# WeatherStation.net
KiCad netlist of a schematic drawn in EAGLE
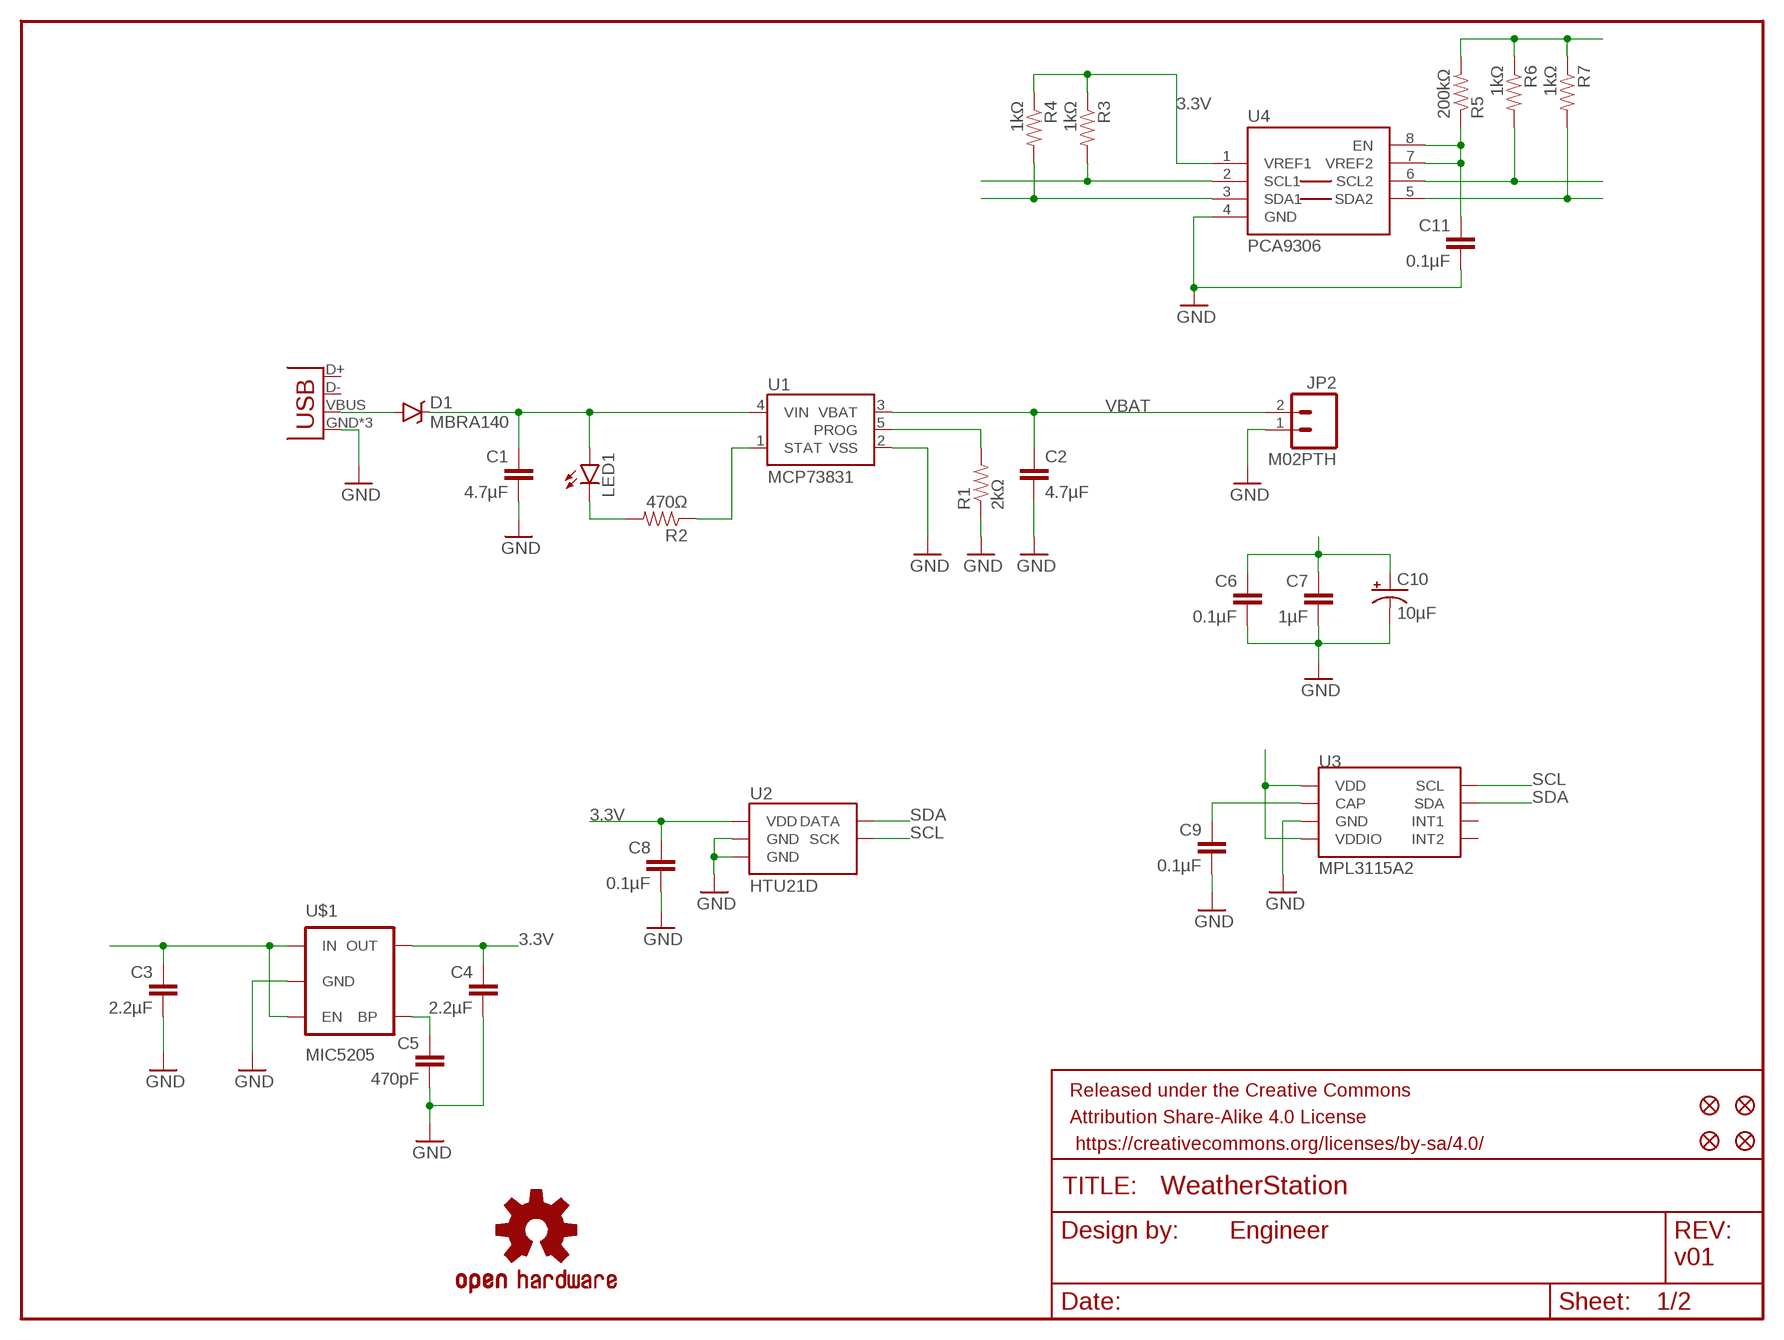
[diagram p0: schematic, sheet 1]
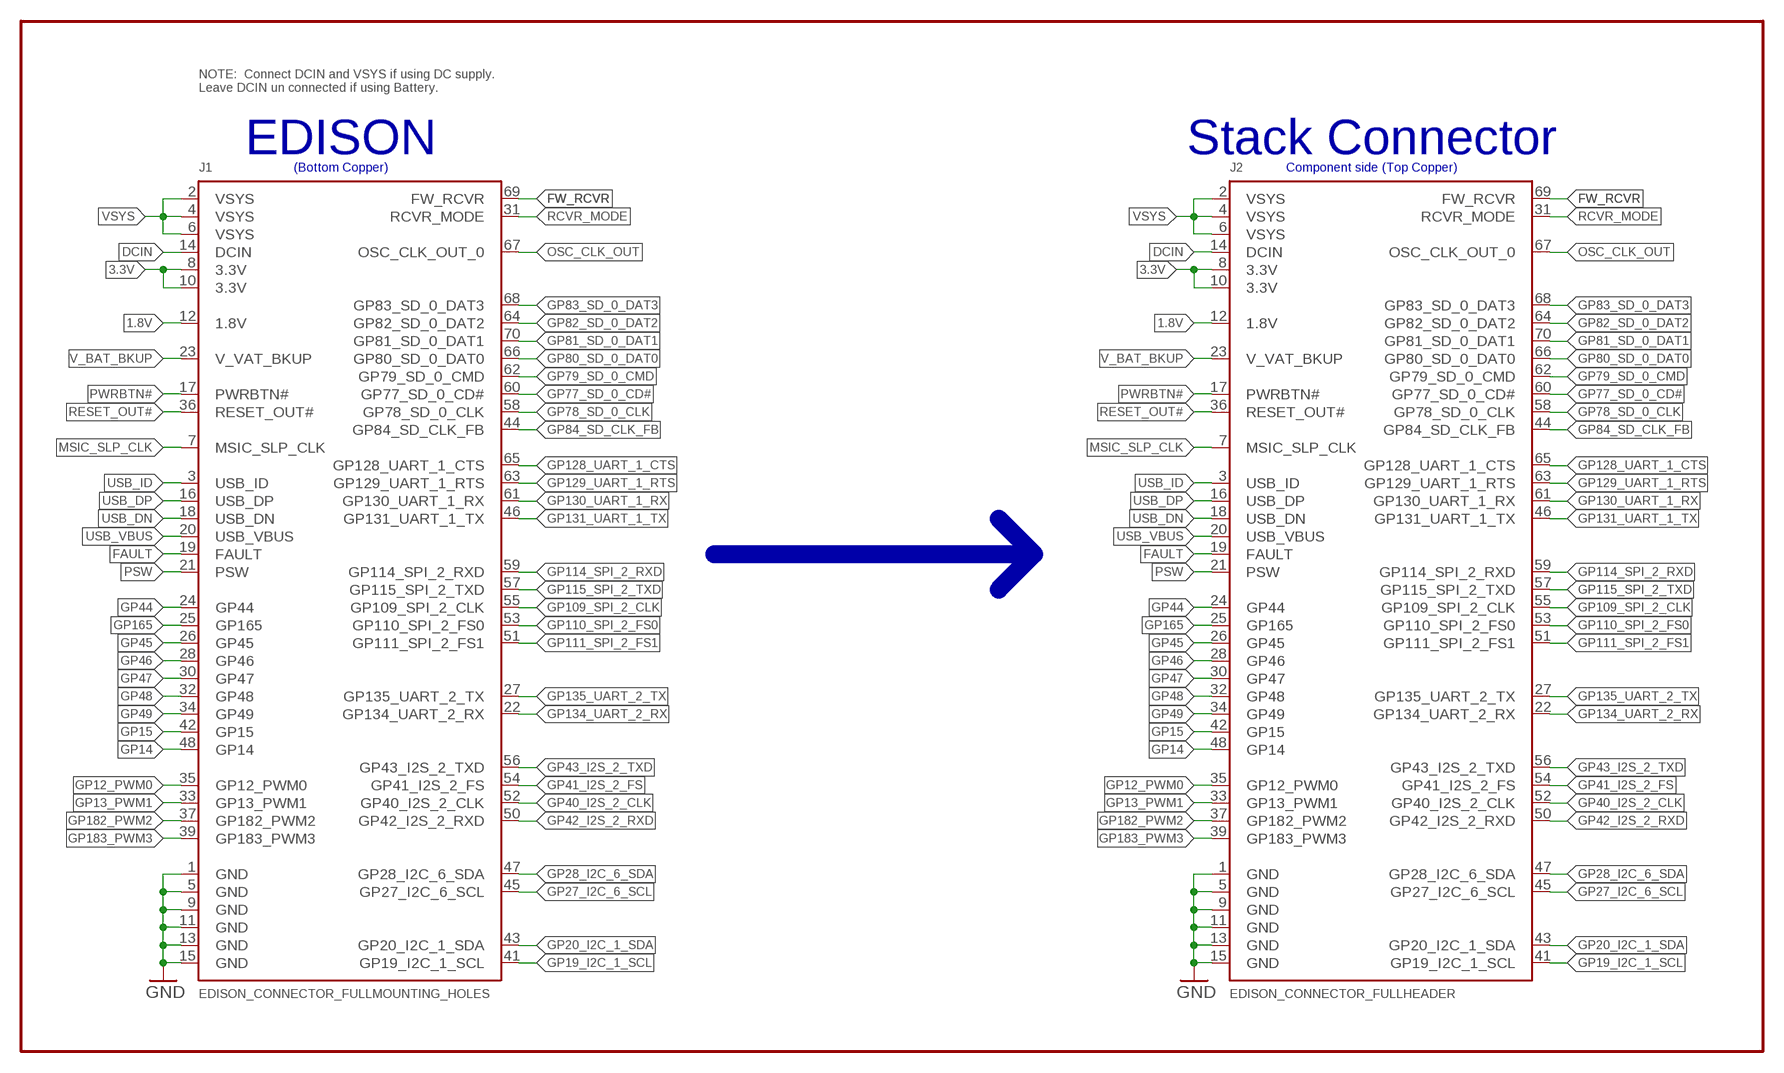
[diagram p1: schematic, sheet 2]

(export (version "E")
  (design (tool "Eeschema 10.0.6"))
  (components
    (comp (ref "C1")
      (value "4.7µF")
      (footprint "eagle-import:0805")
      (libsource (lib "eagle-import") (part "CAP0805"))
    )
    (comp (ref "C2")
      (value "4.7µF")
      (footprint "eagle-import:0805")
      (libsource (lib "eagle-import") (part "CAP0805"))
    )
    (comp (ref "C3")
      (value "2.2µF")
      (footprint "eagle-import:0805")
      (libsource (lib "eagle-import") (part "CAP0805"))
    )
    (comp (ref "C4")
      (value "2.2µF")
      (footprint "eagle-import:0805")
      (libsource (lib "eagle-import") (part "CAP0805"))
    )
    (comp (ref "C5")
      (value "470pF")
      (footprint "eagle-import:0805")
      (libsource (lib "eagle-import") (part "CAP0805"))
    )
    (comp (ref "C6")
      (value "0.1µF")
      (footprint "eagle-import:0805")
      (libsource (lib "eagle-import") (part "CAP0805"))
    )
    (comp (ref "C7")
      (value "1µF")
      (footprint "eagle-import:0805")
      (libsource (lib "eagle-import") (part "CAP0805"))
    )
    (comp (ref "C8")
      (value "0.1µF")
      (footprint "eagle-import:0805")
      (libsource (lib "eagle-import") (part "CAP0805"))
    )
    (comp (ref "C9")
      (value "0.1µF")
      (footprint "eagle-import:0805")
      (libsource (lib "eagle-import") (part "CAP0805"))
    )
    (comp (ref "C10")
      (value "10µF")
      (footprint "eagle-import:EIA3216")
      (libsource (lib "eagle-import") (part "CAP_POL1206"))
    )
    (comp (ref "C11")
      (value "0.1µF")
      (footprint "eagle-import:0805")
      (libsource (lib "eagle-import") (part "CAP0805"))
    )
    (comp (ref "D1")
      (value "MBRA140")
      (footprint "eagle-import:SMA-DIODE")
      (libsource (lib "eagle-import") (part "MBRA140"))
    )
    (comp (ref "FID1")
      (value "FIDUCIAL1X2")
      (footprint "eagle-import:FIDUCIAL-1X2")
      (libsource (lib "eagle-import") (part "FIDUCIAL1X2"))
    )
    (comp (ref "FID2")
      (value "FIDUCIAL1X2")
      (footprint "eagle-import:FIDUCIAL-1X2")
      (libsource (lib "eagle-import") (part "FIDUCIAL1X2"))
    )
    (comp (ref "FID3")
      (value "FIDUCIAL1X2")
      (footprint "eagle-import:FIDUCIAL-1X2")
      (libsource (lib "eagle-import") (part "FIDUCIAL1X2"))
    )
    (comp (ref "FID4")
      (value "FIDUCIAL1X2")
      (footprint "eagle-import:FIDUCIAL-1X2")
      (libsource (lib "eagle-import") (part "FIDUCIAL1X2"))
    )
    (comp (ref "FRAME1")
      (value "FRAME-LETTER")
      (footprint "eagle-import:CREATIVE_COMMONS")
      (libsource (lib "eagle-import") (part "FRAME-LETTER"))
    )
    (comp (ref "JP1")
      (value "USB-MICROB")
      (footprint "eagle-import:USB-MICROB")
      (libsource (lib "eagle-import") (part "USB-MICROB"))
    )
    (comp (ref "JP2")
      (value "M02PTH")
      (footprint "eagle-import:1X02")
      (libsource (lib "eagle-import") (part "M02PTH"))
    )
    (comp (ref "LED1")
      (value "LED0603")
      (footprint "eagle-import:LED-0603")
      (libsource (lib "eagle-import") (part "LED0603"))
    )
    (comp (ref "LOGO1")
      (value "OSHW-LOGOS")
      (footprint "eagle-import:OSHW-LOGO-S")
      (libsource (lib "eagle-import") (part "OSHW-LOGOS"))
    )
    (comp (ref "R1")
      (value "2kΩ")
      (footprint "eagle-import:0603-RES")
      (libsource (lib "eagle-import") (part "RESISTOR0603-RES"))
    )
    (comp (ref "R2")
      (value "470Ω")
      (footprint "eagle-import:0603-RES")
      (libsource (lib "eagle-import") (part "RESISTOR0603-RES"))
    )
    (comp (ref "R3")
      (value "1kΩ")
      (footprint "eagle-import:0603-RES")
      (libsource (lib "eagle-import") (part "RESISTOR0603-RES"))
    )
    (comp (ref "R4")
      (value "1kΩ")
      (footprint "eagle-import:0603-RES")
      (libsource (lib "eagle-import") (part "RESISTOR0603-RES"))
    )
    (comp (ref "R5")
      (value "200kΩ")
      (footprint "eagle-import:0603-RES")
      (libsource (lib "eagle-import") (part "RESISTOR0603-RES"))
    )
    (comp (ref "R6")
      (value "1kΩ")
      (footprint "eagle-import:0603-RES")
      (libsource (lib "eagle-import") (part "RESISTOR0603-RES"))
    )
    (comp (ref "R7")
      (value "1kΩ")
      (footprint "eagle-import:0603-RES")
      (libsource (lib "eagle-import") (part "RESISTOR0603-RES"))
    )
    (comp (ref "U$1")
      (value "MIC5205")
      (footprint "eagle-import:SOT23-5")
      (libsource (lib "eagle-import") (part "V_REG_MIC52053.3V"))
    )
    (comp (ref "U1")
      (value "MCP73831")
      (footprint "eagle-import:SOT23-5")
      (libsource (lib "eagle-import") (part "MCP73831"))
    )
    (comp (ref "U2")
      (value "HTU21D")
      (footprint "eagle-import:HTU21D")
      (libsource (lib "eagle-import") (part "HTU21DSMD"))
    )
    (comp (ref "U3")
      (value "MPL3115A2")
      (footprint "eagle-import:LGA8")
      (libsource (lib "eagle-import") (part "MPL3115A2LGA8"))
    )
    (comp (ref "U4")
      (value "PCA9306")
      (footprint "eagle-import:PSOP-8")
      (libsource (lib "eagle-import") (part "PCA9306"))
    )
    (comp (ref "J1")
      (value "EDISON_CONNECTOR_FULLMOUNTING_HOLES")
      (footprint "eagle-import:EDISON_DAUGHTER")
      (libsource (lib "eagle-import") (part "EDISON_CONNECTOR_FULLMOUNTING_HOLES"))
    )
    (comp (ref "J2")
      (value "EDISON_CONNECTOR_FULLHEADER")
      (footprint "eagle-import:DF40C-70DP-0.4(51)")
      (libsource (lib "eagle-import") (part "EDISON_CONNECTOR_FULLHEADER"))
    )
  )
  (nets
    (net (code "1") (name "1.8V") (class "Default")
      (node (ref "J1") (pin "12") (pinfunction "1.8V_12") (pintype "bidirectional"))
      (node (ref "J2") (pin "12") (pinfunction "1.8V_12") (pintype "bidirectional"))
      (node (ref "R5") (pin "2") (pinfunction "2_2") (pintype "passive"))
      (node (ref "R6") (pin "1") (pinfunction "1_1") (pintype "passive"))
      (node (ref "R7") (pin "1") (pinfunction "1_1") (pintype "passive"))
    )
    (net (code "2") (name "3.3V") (class "Default")
      (node (ref "C10") (pin "A") (pinfunction "+_A") (pintype "passive"))
      (node (ref "C4") (pin "1") (pinfunction "1_1") (pintype "passive"))
      (node (ref "C6") (pin "1") (pinfunction "1_1") (pintype "passive"))
      (node (ref "C7") (pin "1") (pinfunction "1_1") (pintype "passive"))
      (node (ref "C8") (pin "1") (pinfunction "1_1") (pintype "passive"))
      (node (ref "J1") (pin "10") (pinfunction "3.3V_10") (pintype "bidirectional"))
      (node (ref "J1") (pin "8") (pinfunction "3.3V_8") (pintype "bidirectional"))
      (node (ref "J2") (pin "10") (pinfunction "3.3V_10") (pintype "bidirectional"))
      (node (ref "J2") (pin "8") (pinfunction "3.3V_8") (pintype "bidirectional"))
      (node (ref "R3") (pin "1") (pinfunction "1_1") (pintype "passive"))
      (node (ref "R4") (pin "1") (pinfunction "1_1") (pintype "passive"))
      (node (ref "U$1") (pin "5") (pinfunction "OUT_5") (pintype "passive"))
      (node (ref "U2") (pin "VDD") (pinfunction "VDD_VDD") (pintype "power_in"))
      (node (ref "U3") (pin "1") (pinfunction "VDD_1") (pintype "power_in"))
      (node (ref "U3") (pin "4") (pinfunction "VDDIO_4") (pintype "power_in"))
      (node (ref "U4") (pin "1") (pinfunction "VREF1_1") (pintype "bidirectional"))
    )
    (net (code "3") (name "DCIN") (class "Default")
      (node (ref "J1") (pin "14") (pinfunction "DCIN_14") (pintype "bidirectional"))
      (node (ref "J2") (pin "14") (pinfunction "DCIN_14") (pintype "bidirectional"))
    )
    (net (code "4") (name "FAULT") (class "Default")
      (node (ref "J1") (pin "19") (pinfunction "FAULT_19") (pintype "bidirectional"))
      (node (ref "J2") (pin "19") (pinfunction "FAULT_19") (pintype "bidirectional"))
    )
    (net (code "5") (name "FW_RCVR") (class "Default")
      (node (ref "J1") (pin "69") (pinfunction "FW_RCVR_69") (pintype "bidirectional"))
      (node (ref "J2") (pin "69") (pinfunction "FW_RCVR_69") (pintype "bidirectional"))
    )
    (net (code "6") (name "GND") (class "Default")
      (node (ref "C1") (pin "2") (pinfunction "2_2") (pintype "passive"))
      (node (ref "C10") (pin "C") (pinfunction "-_C") (pintype "passive"))
      (node (ref "C11") (pin "2") (pinfunction "2_2") (pintype "passive"))
      (node (ref "C2") (pin "2") (pinfunction "2_2") (pintype "passive"))
      (node (ref "C3") (pin "2") (pinfunction "2_2") (pintype "passive"))
      (node (ref "C4") (pin "2") (pinfunction "2_2") (pintype "passive"))
      (node (ref "C5") (pin "2") (pinfunction "2_2") (pintype "passive"))
      (node (ref "C6") (pin "2") (pinfunction "2_2") (pintype "passive"))
      (node (ref "C7") (pin "2") (pinfunction "2_2") (pintype "passive"))
      (node (ref "C8") (pin "2") (pinfunction "2_2") (pintype "passive"))
      (node (ref "C9") (pin "2") (pinfunction "2_2") (pintype "passive"))
      (node (ref "J1") (pin "1") (pinfunction "GND_1") (pintype "bidirectional"))
      (node (ref "J1") (pin "11") (pinfunction "GND_11") (pintype "bidirectional"))
      (node (ref "J1") (pin "13") (pinfunction "GND_13") (pintype "bidirectional"))
      (node (ref "J1") (pin "15") (pinfunction "GND_15") (pintype "bidirectional"))
      (node (ref "J1") (pin "5") (pinfunction "GND_5") (pintype "bidirectional"))
      (node (ref "J1") (pin "9") (pinfunction "GND_9") (pintype "bidirectional"))
      (node (ref "J2") (pin "1") (pinfunction "GND_1") (pintype "bidirectional"))
      (node (ref "J2") (pin "11") (pinfunction "GND_11") (pintype "bidirectional"))
      (node (ref "J2") (pin "13") (pinfunction "GND_13") (pintype "bidirectional"))
      (node (ref "J2") (pin "15") (pinfunction "GND_15") (pintype "bidirectional"))
      (node (ref "J2") (pin "5") (pinfunction "GND_5") (pintype "bidirectional"))
      (node (ref "J2") (pin "9") (pinfunction "GND_9") (pintype "bidirectional"))
      (node (ref "JP1") (pin "GND") (pinfunction "GND_GND") (pintype "bidirectional"))
      (node (ref "JP1") (pin "MT1") (pinfunction "GND_MT1") (pintype "bidirectional"))
      (node (ref "JP1") (pin "MT2") (pinfunction "GND_MT2") (pintype "bidirectional"))
      (node (ref "JP2") (pin "1") (pinfunction "1_1") (pintype "passive"))
      (node (ref "R1") (pin "1") (pinfunction "1_1") (pintype "passive"))
      (node (ref "U$1") (pin "2") (pinfunction "GND_2") (pintype "input"))
      (node (ref "U1") (pin "2") (pinfunction "VSS_2") (pintype "power_in"))
      (node (ref "U2") (pin "7") (pinfunction "GND_7") (pintype "power_in"))
      (node (ref "U2") (pin "GND") (pinfunction "GND_GND") (pintype "power_in"))
      (node (ref "U3") (pin "3") (pinfunction "GND_3") (pintype "power_in"))
      (node (ref "U4") (pin "4") (pinfunction "GND_4") (pintype "bidirectional"))
    )
    (net (code "7") (name "GP12_PWM0") (class "Default")
      (node (ref "J1") (pin "35") (pinfunction "GP12_PWM0_35") (pintype "bidirectional"))
      (node (ref "J2") (pin "35") (pinfunction "GP12_PWM0_35") (pintype "bidirectional"))
    )
    (net (code "8") (name "GP13_PWM1") (class "Default")
      (node (ref "J1") (pin "33") (pinfunction "GP13_PWM1_33") (pintype "bidirectional"))
      (node (ref "J2") (pin "33") (pinfunction "GP13_PWM1_33") (pintype "bidirectional"))
    )
    (net (code "9") (name "GP14") (class "Default")
      (node (ref "J1") (pin "48") (pinfunction "GP14_48") (pintype "bidirectional"))
      (node (ref "J2") (pin "48") (pinfunction "GP14_48") (pintype "bidirectional"))
    )
    (net (code "10") (name "GP15") (class "Default")
      (node (ref "J1") (pin "42") (pinfunction "GP15_42") (pintype "bidirectional"))
      (node (ref "J2") (pin "42") (pinfunction "GP15_42") (pintype "bidirectional"))
    )
    (net (code "11") (name "GP19_I2C_1_SCL") (class "Default")
      (node (ref "J1") (pin "41") (pinfunction "GP19_I2C_1_SCL_41") (pintype "bidirectional"))
      (node (ref "J2") (pin "41") (pinfunction "GP19_I2C_1_SCL_41") (pintype "bidirectional"))
    )
    (net (code "12") (name "GP20_I2C_1_SDA") (class "Default")
      (node (ref "J1") (pin "43") (pinfunction "GP20_I2C_1_SDA_43") (pintype "bidirectional"))
      (node (ref "J2") (pin "43") (pinfunction "GP20_I2C_1_SDA_43") (pintype "bidirectional"))
    )
    (net (code "13") (name "GP27_I2C_6_SCL") (class "Default")
      (node (ref "J1") (pin "45") (pinfunction "GP27_I2C_6_SCL_45") (pintype "bidirectional"))
      (node (ref "J2") (pin "45") (pinfunction "GP27_I2C_6_SCL_45") (pintype "bidirectional"))
    )
    (net (code "14") (name "GP28_I2C_6_SDA") (class "Default")
      (node (ref "J1") (pin "47") (pinfunction "GP28_I2C_6_SDA_47") (pintype "bidirectional"))
      (node (ref "J2") (pin "47") (pinfunction "GP28_I2C_6_SDA_47") (pintype "bidirectional"))
    )
    (net (code "15") (name "GP40_I2S_2_CLK") (class "Default")
      (node (ref "J1") (pin "52") (pinfunction "GP40_I2S_2_CLK_52") (pintype "bidirectional"))
      (node (ref "J2") (pin "52") (pinfunction "GP40_I2S_2_CLK_52") (pintype "bidirectional"))
    )
    (net (code "16") (name "GP41_I2S_2_FS") (class "Default")
      (node (ref "J1") (pin "54") (pinfunction "GP41_I2S_2_FS_54") (pintype "bidirectional"))
      (node (ref "J2") (pin "54") (pinfunction "GP41_I2S_2_FS_54") (pintype "bidirectional"))
    )
    (net (code "17") (name "GP42_I2S_2_RXD") (class "Default")
      (node (ref "J1") (pin "50") (pinfunction "GP42_I2S_2_RXD_50") (pintype "bidirectional"))
      (node (ref "J2") (pin "50") (pinfunction "GP42_I2S_2_RXD_50") (pintype "bidirectional"))
    )
    (net (code "18") (name "GP43_I2S_2_TXD") (class "Default")
      (node (ref "J1") (pin "56") (pinfunction "GP43_I2S_2_TXD_56") (pintype "bidirectional"))
      (node (ref "J2") (pin "56") (pinfunction "GP43_I2S_2_TXD_56") (pintype "bidirectional"))
    )
    (net (code "19") (name "GP44") (class "Default")
      (node (ref "J1") (pin "24") (pinfunction "GP44_24") (pintype "bidirectional"))
      (node (ref "J2") (pin "24") (pinfunction "GP44_24") (pintype "bidirectional"))
    )
    (net (code "20") (name "GP45") (class "Default")
      (node (ref "J1") (pin "26") (pinfunction "GP45_26") (pintype "bidirectional"))
      (node (ref "J2") (pin "26") (pinfunction "GP45_26") (pintype "bidirectional"))
    )
    (net (code "21") (name "GP46") (class "Default")
      (node (ref "J1") (pin "28") (pinfunction "GP46_28") (pintype "bidirectional"))
      (node (ref "J2") (pin "28") (pinfunction "GP46_28") (pintype "bidirectional"))
    )
    (net (code "22") (name "GP47") (class "Default")
      (node (ref "J1") (pin "30") (pinfunction "GP47_30") (pintype "bidirectional"))
      (node (ref "J2") (pin "30") (pinfunction "GP47_30") (pintype "bidirectional"))
    )
    (net (code "23") (name "GP48") (class "Default")
      (node (ref "J1") (pin "32") (pinfunction "GP48_32") (pintype "bidirectional"))
      (node (ref "J2") (pin "32") (pinfunction "GP48_32") (pintype "bidirectional"))
    )
    (net (code "24") (name "GP49") (class "Default")
      (node (ref "J1") (pin "34") (pinfunction "GP49_34") (pintype "bidirectional"))
      (node (ref "J2") (pin "34") (pinfunction "GP49_34") (pintype "bidirectional"))
    )
    (net (code "25") (name "GP77_SD_0_CD#") (class "Default")
      (node (ref "J1") (pin "60") (pinfunction "GP77_SD_0_CD#_60") (pintype "bidirectional"))
      (node (ref "J2") (pin "60") (pinfunction "GP77_SD_0_CD#_60") (pintype "bidirectional"))
    )
    (net (code "26") (name "GP78_SD_0_CLK") (class "Default")
      (node (ref "J1") (pin "58") (pinfunction "GP78_SD_0_CLK_58") (pintype "bidirectional"))
      (node (ref "J2") (pin "58") (pinfunction "GP78_SD_0_CLK_58") (pintype "bidirectional"))
    )
    (net (code "27") (name "GP79_SD_0_CMD") (class "Default")
      (node (ref "J1") (pin "62") (pinfunction "GP79_SD_0_CMD_62") (pintype "bidirectional"))
      (node (ref "J2") (pin "62") (pinfunction "GP79_SD_0_CMD_62") (pintype "bidirectional"))
    )
    (net (code "28") (name "GP80_SD_0_DAT0") (class "Default")
      (node (ref "J1") (pin "66") (pinfunction "GP80_SD_0_DAT0_66") (pintype "bidirectional"))
      (node (ref "J2") (pin "66") (pinfunction "GP80_SD_0_DAT0_66") (pintype "bidirectional"))
    )
    (net (code "29") (name "GP81_SD_0_DAT1") (class "Default")
      (node (ref "J1") (pin "70") (pinfunction "GP81_SD_0_DAT1_70") (pintype "bidirectional"))
      (node (ref "J2") (pin "70") (pinfunction "GP81_SD_0_DAT1_70") (pintype "bidirectional"))
    )
    (net (code "30") (name "GP82_SD_0_DAT2") (class "Default")
      (node (ref "J1") (pin "64") (pinfunction "GP82_SD_0_DAT2_64") (pintype "bidirectional"))
      (node (ref "J2") (pin "64") (pinfunction "GP82_SD_0_DAT2_64") (pintype "bidirectional"))
    )
    (net (code "31") (name "GP83_SD_0_DAT3") (class "Default")
      (node (ref "J1") (pin "68") (pinfunction "GP83_SD_0_DAT3_68") (pintype "bidirectional"))
      (node (ref "J2") (pin "68") (pinfunction "GP83_SD_0_DAT3_68") (pintype "bidirectional"))
    )
    (net (code "32") (name "GP84_SD_CLK_FB") (class "Default")
      (node (ref "J1") (pin "44") (pinfunction "GP84_SD_CLK_FB_44") (pintype "bidirectional"))
      (node (ref "J2") (pin "44") (pinfunction "GP84_SD_CLK_FB_44") (pintype "bidirectional"))
    )
    (net (code "33") (name "GP109_SPI_2_CLK") (class "Default")
      (node (ref "J1") (pin "55") (pinfunction "GP109_SPI_2_CLK_55") (pintype "bidirectional"))
      (node (ref "J2") (pin "55") (pinfunction "GP109_SPI_2_CLK_55") (pintype "bidirectional"))
    )
    (net (code "34") (name "GP110_SPI_2_FS0") (class "Default")
      (node (ref "J1") (pin "53") (pinfunction "GP110_SPI_2_FS0_53") (pintype "bidirectional"))
      (node (ref "J2") (pin "53") (pinfunction "GP110_SPI_2_FS0_53") (pintype "bidirectional"))
    )
    (net (code "35") (name "GP111_SPI_2_FS1") (class "Default")
      (node (ref "J1") (pin "51") (pinfunction "GP111_SPI_2_FS1_51") (pintype "bidirectional"))
      (node (ref "J2") (pin "51") (pinfunction "GP111_SPI_2_FS1_51") (pintype "bidirectional"))
    )
    (net (code "36") (name "GP114_SPI_2_RXD") (class "Default")
      (node (ref "J1") (pin "59") (pinfunction "GP114_SPI_2_RXD_59") (pintype "bidirectional"))
      (node (ref "J2") (pin "59") (pinfunction "GP114_SPI_2_RXD_59") (pintype "bidirectional"))
    )
    (net (code "37") (name "GP115_SPI_2_TXD") (class "Default")
      (node (ref "J1") (pin "57") (pinfunction "GP115_SPI_2_TXD_57") (pintype "bidirectional"))
      (node (ref "J2") (pin "57") (pinfunction "GP115_SPI_2_TXD_57") (pintype "bidirectional"))
    )
    (net (code "38") (name "GP128_UART_1_CTS") (class "Default")
      (node (ref "J1") (pin "65") (pinfunction "GP128_UART_1_CTS_65") (pintype "bidirectional"))
      (node (ref "J2") (pin "65") (pinfunction "GP128_UART_1_CTS_65") (pintype "bidirectional"))
    )
    (net (code "39") (name "GP129_UART_1_RTS") (class "Default")
      (node (ref "J1") (pin "63") (pinfunction "GP129_UART_1_RTS_63") (pintype "bidirectional"))
      (node (ref "J2") (pin "63") (pinfunction "GP129_UART_1_RTS_63") (pintype "bidirectional"))
    )
    (net (code "40") (name "GP130_UART_1_RX") (class "Default")
      (node (ref "J1") (pin "61") (pinfunction "GP130_UART_1_RX_61") (pintype "bidirectional"))
      (node (ref "J2") (pin "61") (pinfunction "GP130_UART_1_RX_61") (pintype "bidirectional"))
    )
    (net (code "41") (name "GP131_UART_1_TX") (class "Default")
      (node (ref "J1") (pin "46") (pinfunction "GP131_UART_1_TX_46") (pintype "bidirectional"))
      (node (ref "J2") (pin "46") (pinfunction "GP131_UART_1_TX_46") (pintype "bidirectional"))
    )
    (net (code "42") (name "GP134_UART_2_RX") (class "Default")
      (node (ref "J1") (pin "22") (pinfunction "GP134_UART_2_RX_22") (pintype "bidirectional"))
      (node (ref "J2") (pin "22") (pinfunction "GP134_UART_2_RX_22") (pintype "bidirectional"))
    )
    (net (code "43") (name "GP135_UART_2_TX") (class "Default")
      (node (ref "J1") (pin "27") (pinfunction "GP135_UART_2_TX_27") (pintype "bidirectional"))
      (node (ref "J2") (pin "27") (pinfunction "GP135_UART_2_TX_27") (pintype "bidirectional"))
    )
    (net (code "44") (name "GP165") (class "Default")
      (node (ref "J1") (pin "25") (pinfunction "GP165_25") (pintype "bidirectional"))
      (node (ref "J2") (pin "25") (pinfunction "GP165_25") (pintype "bidirectional"))
    )
    (net (code "45") (name "GP182_PWM2") (class "Default")
      (node (ref "J1") (pin "37") (pinfunction "GP182_PWM2_37") (pintype "bidirectional"))
      (node (ref "J2") (pin "37") (pinfunction "GP182_PWM2_37") (pintype "bidirectional"))
    )
    (net (code "46") (name "GP183_PWM3") (class "Default")
      (node (ref "J1") (pin "39") (pinfunction "GP183_PWM3_39") (pintype "bidirectional"))
      (node (ref "J2") (pin "39") (pinfunction "GP183_PWM3_39") (pintype "bidirectional"))
    )
    (net (code "47") (name "MSIC_SLP_CLK") (class "Default")
      (node (ref "J1") (pin "7") (pinfunction "MSIC_SLP_CLK_7") (pintype "bidirectional"))
      (node (ref "J2") (pin "7") (pinfunction "MSIC_SLP_CLK_7") (pintype "bidirectional"))
    )
    (net (code "48") (name "Net-(D1-PadA)") (class "Default")
      (node (ref "D1") (pin "A") (pinfunction "A_A") (pintype "passive"))
      (node (ref "JP1") (pin "VBUS") (pinfunction "VBUS_VBUS") (pintype "bidirectional"))
    )
    (net (code "49") (name "Net-(LED1-PadC)") (class "Default")
      (node (ref "LED1") (pin "C") (pinfunction "C_C") (pintype "passive"))
      (node (ref "R2") (pin "2") (pinfunction "2_2") (pintype "passive"))
    )
    (net (code "50") (name "Net-(U$1-BP)") (class "Default")
      (node (ref "C5") (pin "1") (pinfunction "1_1") (pintype "passive"))
      (node (ref "U$1") (pin "4") (pinfunction "BP_4") (pintype "input"))
    )
    (net (code "51") (name "Net-(U1-PROG)") (class "Default")
      (node (ref "R1") (pin "2") (pinfunction "2_2") (pintype "passive"))
      (node (ref "U1") (pin "5") (pinfunction "PROG_5") (pintype "input"))
    )
    (net (code "52") (name "Net-(U1-STAT)") (class "Default")
      (node (ref "R2") (pin "1") (pinfunction "1_1") (pintype "passive"))
      (node (ref "U1") (pin "1") (pinfunction "STAT_1") (pintype "output"))
    )
    (net (code "53") (name "Net-(U1-VIN)") (class "Default")
      (node (ref "C1") (pin "1") (pinfunction "1_1") (pintype "passive"))
      (node (ref "D1") (pin "C") (pinfunction "C_C") (pintype "passive"))
      (node (ref "LED1") (pin "A") (pinfunction "A_A") (pintype "passive"))
      (node (ref "U1") (pin "4") (pinfunction "VIN_4") (pintype "power_in"))
    )
    (net (code "54") (name "Net-(U3-CAP)") (class "Default")
      (node (ref "C9") (pin "1") (pinfunction "1_1") (pintype "passive"))
      (node (ref "U3") (pin "2") (pinfunction "CAP_2") (pintype "power_in"))
    )
    (net (code "55") (name "Net-(U4-EN)") (class "Default")
      (node (ref "C11") (pin "1") (pinfunction "1_1") (pintype "passive"))
      (node (ref "R5") (pin "1") (pinfunction "1_1") (pintype "passive"))
      (node (ref "U4") (pin "7") (pinfunction "VREF2_7") (pintype "bidirectional"))
      (node (ref "U4") (pin "8") (pinfunction "EN_8") (pintype "bidirectional"))
    )
    (net (code "56") (name "Net-(U4-SCL2)") (class "Default")
      (node (ref "R6") (pin "2") (pinfunction "2_2") (pintype "passive"))
      (node (ref "U4") (pin "6") (pinfunction "SCL2_6") (pintype "bidirectional"))
    )
    (net (code "57") (name "Net-(U4-SDA2)") (class "Default")
      (node (ref "R7") (pin "2") (pinfunction "2_2") (pintype "passive"))
      (node (ref "U4") (pin "5") (pinfunction "SDA2_5") (pintype "bidirectional"))
    )
    (net (code "58") (name "OSC_CLK_OUT") (class "Default")
      (node (ref "J1") (pin "67") (pinfunction "OSC_CLK_OUT_0_67") (pintype "bidirectional"))
      (node (ref "J2") (pin "67") (pinfunction "OSC_CLK_OUT_0_67") (pintype "bidirectional"))
    )
    (net (code "59") (name "PSW") (class "Default")
      (node (ref "J1") (pin "21") (pinfunction "PSW_21") (pintype "bidirectional"))
      (node (ref "J2") (pin "21") (pinfunction "PSW_21") (pintype "bidirectional"))
    )
    (net (code "60") (name "PWRBTN#") (class "Default")
      (node (ref "J1") (pin "17") (pinfunction "PWRBTN#_17") (pintype "bidirectional"))
      (node (ref "J2") (pin "17") (pinfunction "PWRBTN#_17") (pintype "bidirectional"))
    )
    (net (code "61") (name "RCVR_MODE") (class "Default")
      (node (ref "J1") (pin "31") (pinfunction "RCVR_MODE_31") (pintype "bidirectional"))
      (node (ref "J2") (pin "31") (pinfunction "RCVR_MODE_31") (pintype "bidirectional"))
    )
    (net (code "62") (name "RESET_OUT#") (class "Default")
      (node (ref "J1") (pin "36") (pinfunction "RESET_OUT#_36") (pintype "bidirectional"))
      (node (ref "J2") (pin "36") (pinfunction "RESET_OUT#_36") (pintype "bidirectional"))
    )
    (net (code "63") (name "SCL") (class "Default")
      (node (ref "R3") (pin "2") (pinfunction "2_2") (pintype "passive"))
      (node (ref "U2") (pin "SCK") (pinfunction "SCK_SCK") (pintype "input"))
      (node (ref "U3") (pin "8") (pinfunction "SCL_8") (pintype "bidirectional"))
      (node (ref "U4") (pin "2") (pinfunction "SCL1_2") (pintype "bidirectional"))
    )
    (net (code "64") (name "SDA") (class "Default")
      (node (ref "R4") (pin "2") (pinfunction "2_2") (pintype "passive"))
      (node (ref "U2") (pin "DATA") (pinfunction "DATA_DATA") (pintype "bidirectional"))
      (node (ref "U3") (pin "7") (pinfunction "SDA_7") (pintype "bidirectional"))
      (node (ref "U4") (pin "3") (pinfunction "SDA1_3") (pintype "bidirectional"))
    )
    (net (code "65") (name "USB_DN") (class "Default")
      (node (ref "J1") (pin "18") (pinfunction "USB_DN_18") (pintype "bidirectional"))
      (node (ref "J2") (pin "18") (pinfunction "USB_DN_18") (pintype "bidirectional"))
    )
    (net (code "66") (name "USB_DP") (class "Default")
      (node (ref "J1") (pin "16") (pinfunction "USB_DP_16") (pintype "bidirectional"))
      (node (ref "J2") (pin "16") (pinfunction "USB_DP_16") (pintype "bidirectional"))
    )
    (net (code "67") (name "USB_ID") (class "Default")
      (node (ref "J1") (pin "3") (pinfunction "USB_ID_3") (pintype "bidirectional"))
      (node (ref "J2") (pin "3") (pinfunction "USB_ID_3") (pintype "bidirectional"))
    )
    (net (code "68") (name "USB_VBUS") (class "Default")
      (node (ref "J1") (pin "20") (pinfunction "USB_VBUS_20") (pintype "bidirectional"))
      (node (ref "J2") (pin "20") (pinfunction "USB_VBUS_20") (pintype "bidirectional"))
    )
    (net (code "69") (name "VBAT") (class "Default")
      (node (ref "C2") (pin "1") (pinfunction "1_1") (pintype "passive"))
      (node (ref "C3") (pin "1") (pinfunction "1_1") (pintype "passive"))
      (node (ref "JP2") (pin "2") (pinfunction "2_2") (pintype "passive"))
      (node (ref "U$1") (pin "1") (pinfunction "IN_1") (pintype "input"))
      (node (ref "U$1") (pin "3") (pinfunction "EN_3") (pintype "input"))
      (node (ref "U1") (pin "3") (pinfunction "VBAT_3") (pintype "power_in"))
    )
    (net (code "70") (name "VSYS") (class "Default")
      (node (ref "J1") (pin "2") (pinfunction "VSYS_2") (pintype "bidirectional"))
      (node (ref "J1") (pin "4") (pinfunction "VSYS_4") (pintype "bidirectional"))
      (node (ref "J1") (pin "6") (pinfunction "VSYS_6") (pintype "bidirectional"))
      (node (ref "J2") (pin "2") (pinfunction "VSYS_2") (pintype "bidirectional"))
      (node (ref "J2") (pin "4") (pinfunction "VSYS_4") (pintype "bidirectional"))
      (node (ref "J2") (pin "6") (pinfunction "VSYS_6") (pintype "bidirectional"))
    )
    (net (code "71") (name "V_BAT_BKUP") (class "Default")
      (node (ref "J1") (pin "23") (pinfunction "V_VAT_BKUP_23") (pintype "bidirectional"))
      (node (ref "J2") (pin "23") (pinfunction "V_VAT_BKUP_23") (pintype "bidirectional"))
    )
    (net (code "72") (name "unconnected-(JP1-PadD+)") (class "Default")
      (node (ref "JP1") (pin "D+") (pinfunction "D+_D+") (pintype "bidirectional"))
    )
    (net (code "73") (name "unconnected-(JP1-PadD-)") (class "Default")
      (node (ref "JP1") (pin "D-") (pinfunction "D-_D-") (pintype "bidirectional"))
    )
    (net (code "74") (name "unconnected-(U3-INT1-Pad6)") (class "Default")
      (node (ref "U3") (pin "6") (pinfunction "INT1_6") (pintype "output"))
    )
    (net (code "75") (name "unconnected-(U3-INT2-Pad5)") (class "Default")
      (node (ref "U3") (pin "5") (pinfunction "INT2_5") (pintype "output"))
    )
  )
)
